# quadcopter.net
KiCad netlist of a schematic drawn in EAGLE
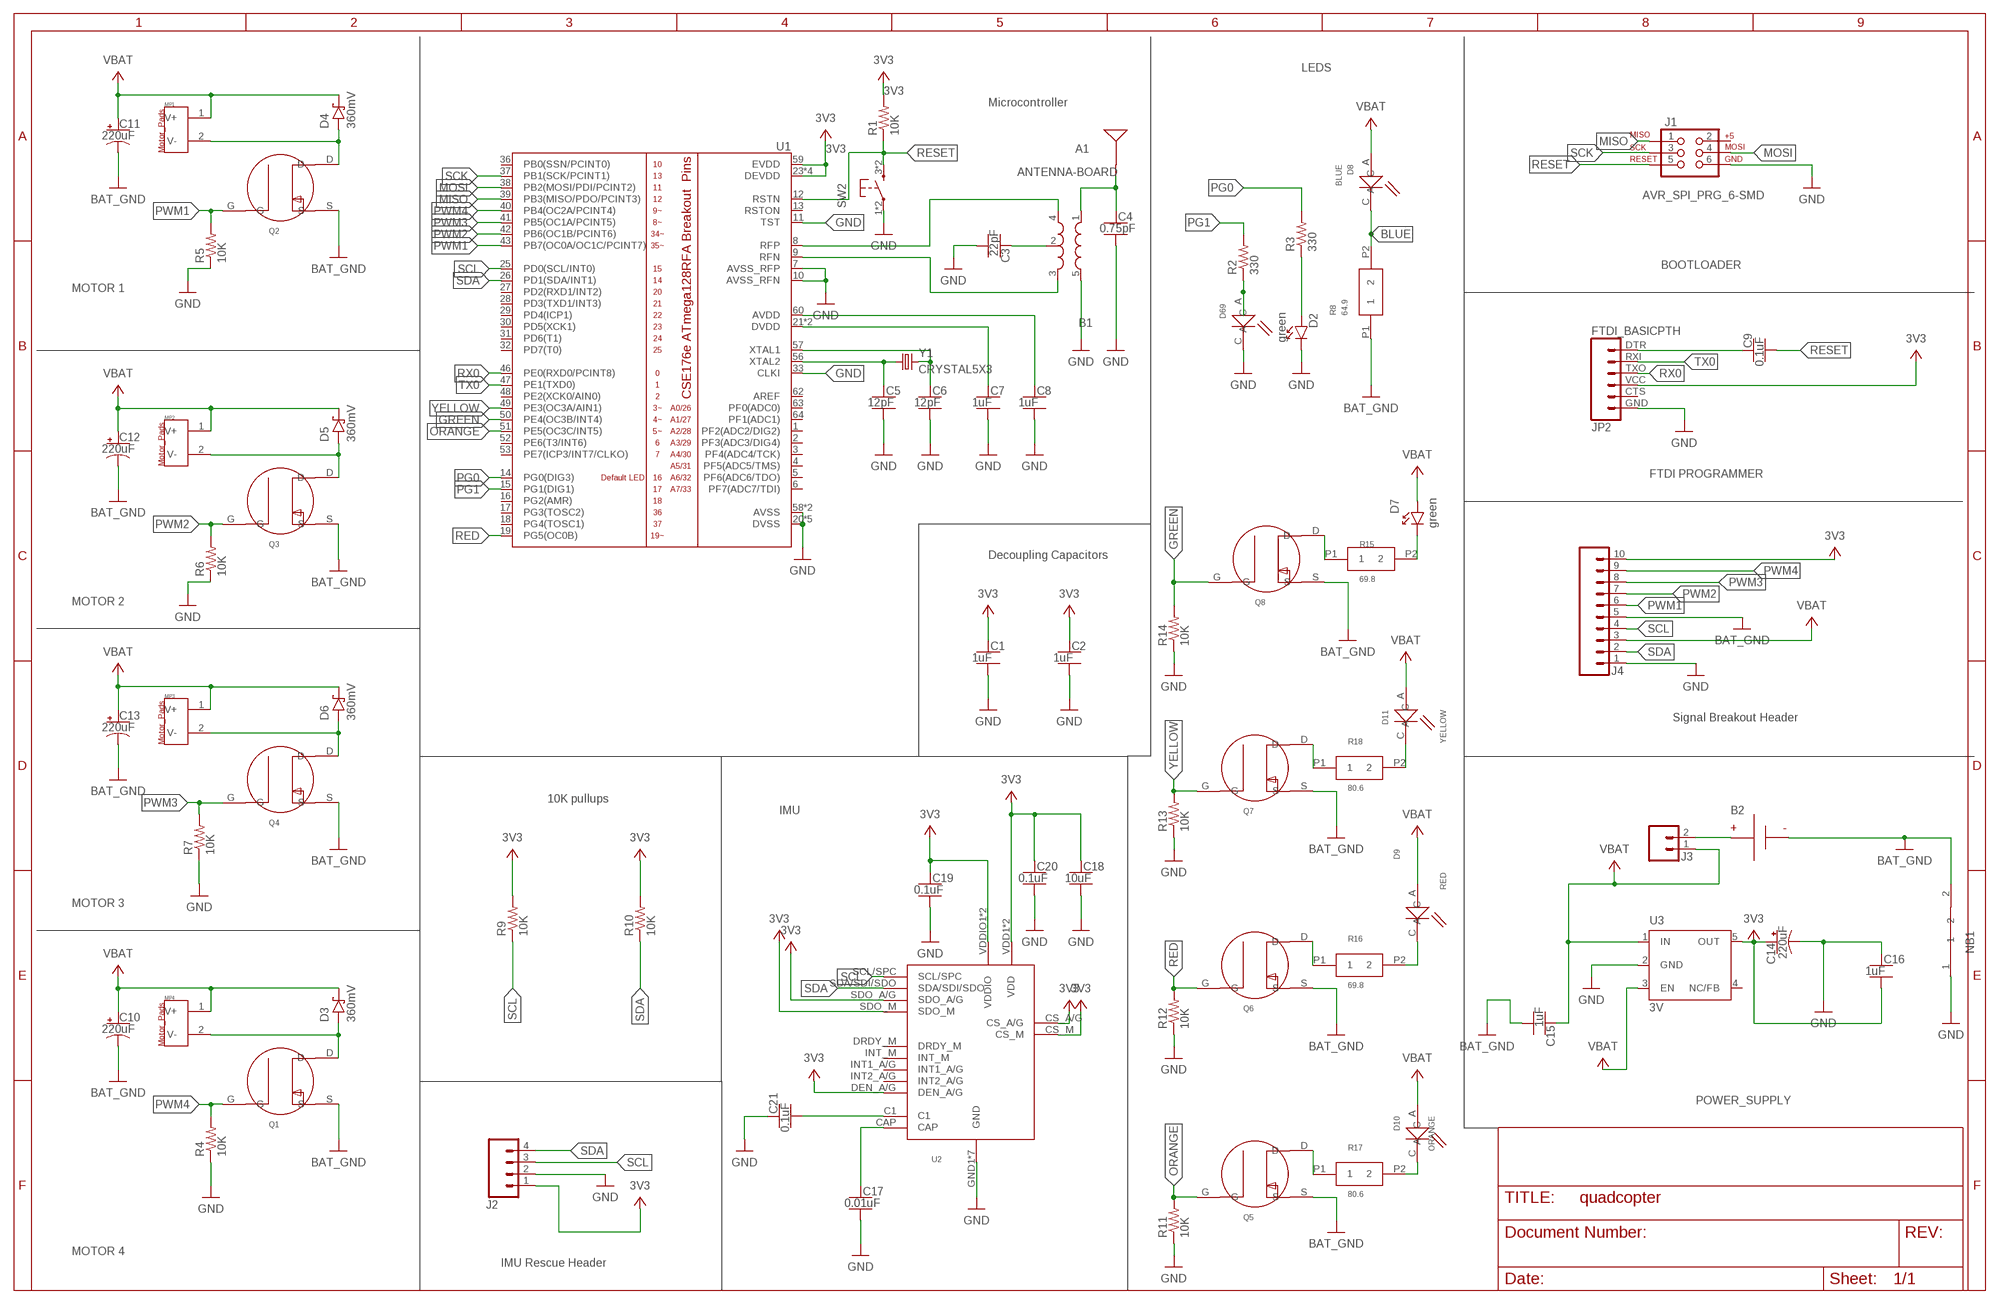
[diagram p0: schematic, sheet 1]

(export (version "E")
  (design (tool "Eeschema 10.0.6"))
  (components
    (comp (ref "A1")
      (value "ANTENNA-BOARD")
      (footprint "eagle-import:ANT_PCB_2.4GHZ_NRF8001_1.6MM_1OZ")
      (fields (field (name "CREATOR") "Swanson"))
      (libsource (lib "eagle-import") (part "ANTENNA-BOARD"))
    )
    (comp (ref "B1")
      (value "BALUN0805")
      (footprint "eagle-import:BALUN")
      (fields
        (field (name "MFR") "Wurth Electronics Inc")
        (field (name "MPN") "748421245")
        (field (name "CREATOR") "Swanson")
        (field (name "REVIEWER") "Swanson")
      )
      (libsource (lib "eagle-import") (part "BALUN0805"))
    )
    (comp (ref "B2")
      (value "BATTERY-SCREW-TERMINAL")
      (footprint "eagle-import:SCREW-TERMINAL-1X2-2.54MM")
      (fields (field (name "CREATOR") "Swanson"))
      (libsource (lib "eagle-import") (part "BATTERY-SCREW-TERMINAL"))
    )
    (comp (ref "C1")
      (value "1uF")
      (footprint "eagle-import:CAPC2012X140_HS")
      (fields
        (field (name "MFR") "Taiyo Yuden")
        (field (name "MPN") "TMK212B7105KG-T")
        (field (name "CREATOR") "Swanson")
        (field (name "REVIEWER") "Swanson")
      )
      (libsource (lib "eagle-import") (part "CAPACITOR-NP_SMD-2012-0805_CERAMIC-1UF"))
    )
    (comp (ref "C2")
      (value "1uF")
      (footprint "eagle-import:CAPC2012X140_HS")
      (fields
        (field (name "MFR") "Taiyo Yuden")
        (field (name "MPN") "TMK212B7105KG-T")
        (field (name "CREATOR") "Swanson")
        (field (name "REVIEWER") "Swanson")
      )
      (libsource (lib "eagle-import") (part "CAPACITOR-NP_SMD-2012-0805_CERAMIC-1UF"))
    )
    (comp (ref "C3")
      (value "22pF")
      (footprint "eagle-import:CAPC2012X140_HS")
      (fields
        (field (name "MFR") "Murata Electronics North America")
        (field (name "MPN") "GRM21A5C2E220JW01D")
        (field (name "CREATOR") "Swanson")
        (field (name "REVIEWER") "Swanson")
      )
      (libsource (lib "eagle-import") (part "CAPACITOR-NP_SMD-2012-0805_CERAMIC-22PF"))
    )
    (comp (ref "C4")
      (value "0.75pF")
      (footprint "eagle-import:CAPC2012X140_HS")
      (fields
        (field (name "MFR") "Murata Electronics North America")
        (field (name "MPN") "GQM2195C2AR75CB01D")
        (field (name "CREATOR") "Swanson")
        (field (name "REVIEWER") "Swanson")
      )
      (libsource (lib "eagle-import") (part "CAPACITOR-NP_SMD-2012-0805_CERAMIC-0.75PF"))
    )
    (comp (ref "C5")
      (value "12pF")
      (footprint "eagle-import:CAPC2012X140_HS")
      (fields
        (field (name "MFR") "Murata Electronics North America")
        (field (name "MPN") "GRM21A5C2E120JW01D")
        (field (name "CREATOR") "Swanson")
        (field (name "REVIEWER") "Swanson")
      )
      (libsource (lib "eagle-import") (part "CAPACITOR-NP_SMD-2012-0805_CERAMIC-12PF"))
    )
    (comp (ref "C6")
      (value "12pF")
      (footprint "eagle-import:CAPC2012X140_HS")
      (fields
        (field (name "MFR") "Murata Electronics North America")
        (field (name "MPN") "GRM21A5C2E120JW01D")
        (field (name "CREATOR") "Swanson")
        (field (name "REVIEWER") "Swanson")
      )
      (libsource (lib "eagle-import") (part "CAPACITOR-NP_SMD-2012-0805_CERAMIC-12PF"))
    )
    (comp (ref "C7")
      (value "1uF")
      (footprint "eagle-import:CAPC2012X140_HS")
      (fields
        (field (name "MFR") "Taiyo Yuden")
        (field (name "MPN") "TMK212B7105KG-T")
        (field (name "CREATOR") "Swanson")
        (field (name "REVIEWER") "Swanson")
      )
      (libsource (lib "eagle-import") (part "CAPACITOR-NP_SMD-2012-0805_CERAMIC-1UF"))
    )
    (comp (ref "C8")
      (value "1uF")
      (footprint "eagle-import:CAPC2012X140_HS")
      (fields
        (field (name "MFR") "Taiyo Yuden")
        (field (name "MPN") "TMK212B7105KG-T")
        (field (name "CREATOR") "Swanson")
        (field (name "REVIEWER") "Swanson")
      )
      (libsource (lib "eagle-import") (part "CAPACITOR-NP_SMD-2012-0805_CERAMIC-1UF"))
    )
    (comp (ref "C9")
      (value "0.1uF")
      (footprint "eagle-import:CAPC2012X140_HS")
      (fields
        (field (name "MFR") "TDK")
        (field (name "MPN") "C2012X7R2A104K125AA")
        (field (name "CREATOR") "Swanson")
        (field (name "REVIEWER") "Swanson")
      )
      (libsource (lib "eagle-import") (part "CAPACITOR-NP_SMD-2012-0805_CERAMIC-0.1UF"))
    )
    (comp (ref "C10")
      (value "220uF")
      (footprint "eagle-import:CAPMP7343X310_HS")
      (fields
        (field (name "MFR") "AVX Corporation")
        (field (name "MPN") "TAJD227K006RNJ")
        (field (name "CREATOR") "Swanson")
        (field (name "REVIEWER") "Swanson")
      )
      (libsource (lib "eagle-import") (part "CAPACITOR-POL_SMD-7043-D_TANTALUM-220UF"))
    )
    (comp (ref "C11")
      (value "220uF")
      (footprint "eagle-import:CAPMP7343X310_HS")
      (fields
        (field (name "MFR") "AVX Corporation")
        (field (name "MPN") "TAJD227K006RNJ")
        (field (name "CREATOR") "Swanson")
        (field (name "REVIEWER") "Swanson")
      )
      (libsource (lib "eagle-import") (part "CAPACITOR-POL_SMD-7043-D_TANTALUM-220UF"))
    )
    (comp (ref "C12")
      (value "220uF")
      (footprint "eagle-import:CAPMP7343X310_HS")
      (fields
        (field (name "MFR") "AVX Corporation")
        (field (name "MPN") "TAJD227K006RNJ")
        (field (name "CREATOR") "Swanson")
        (field (name "REVIEWER") "Swanson")
      )
      (libsource (lib "eagle-import") (part "CAPACITOR-POL_SMD-7043-D_TANTALUM-220UF"))
    )
    (comp (ref "C13")
      (value "220uF")
      (footprint "eagle-import:CAPMP7343X310_HS")
      (fields
        (field (name "MFR") "AVX Corporation")
        (field (name "MPN") "TAJD227K006RNJ")
        (field (name "CREATOR") "Swanson")
        (field (name "REVIEWER") "Swanson")
      )
      (libsource (lib "eagle-import") (part "CAPACITOR-POL_SMD-7043-D_TANTALUM-220UF"))
    )
    (comp (ref "C14")
      (value "220uF")
      (footprint "eagle-import:CAPMP7343X310_HS")
      (fields
        (field (name "MFR") "AVX Corporation")
        (field (name "MPN") "TAJD227K006RNJ")
        (field (name "CREATOR") "Swanson")
        (field (name "REVIEWER") "Swanson")
      )
      (libsource (lib "eagle-import") (part "CAPACITOR-POL_SMD-7043-D_TANTALUM-220UF"))
    )
    (comp (ref "C15")
      (value "1uF")
      (footprint "eagle-import:CAPC2012X140_HS")
      (fields
        (field (name "MFR") "Taiyo Yuden")
        (field (name "MPN") "TMK212B7105KG-T")
        (field (name "CREATOR") "Swanson")
        (field (name "REVIEWER") "Swanson")
      )
      (libsource (lib "eagle-import") (part "CAPACITOR-NP_SMD-2012-0805_CERAMIC-1UF"))
    )
    (comp (ref "C16")
      (value "1uF")
      (footprint "eagle-import:CAPC2012X140_HS")
      (fields
        (field (name "MFR") "Taiyo Yuden")
        (field (name "MPN") "TMK212B7105KG-T")
        (field (name "CREATOR") "Swanson")
        (field (name "REVIEWER") "Swanson")
      )
      (libsource (lib "eagle-import") (part "CAPACITOR-NP_SMD-2012-0805_CERAMIC-1UF"))
    )
    (comp (ref "C17")
      (value "0.01uF")
      (footprint "eagle-import:CAPC2012X140_HS")
      (fields
        (field (name "MFR") "Knowles Syfer")
        (field (name "MPN") "0805J0500104KJT")
        (field (name "CREATOR") "Swanson")
        (field (name "REVIEWER") "Swanson")
      )
      (libsource (lib "eagle-import") (part "CAPACITOR-NP_SMD-2012-0805_CERAMIC-0.01UF"))
    )
    (comp (ref "C18")
      (value "10uF")
      (footprint "eagle-import:CAPC2012X140_HS")
      (fields (field (name "CREATOR") "Swanson") (field (name "REVIEWER") "Swanson"))
      (libsource (lib "eagle-import") (part "CAPACITOR-NP_SMD-2012-0805_CERAMIC-10UF"))
    )
    (comp (ref "C19")
      (value "0.1uF")
      (footprint "eagle-import:CAPC2012X140_HS")
      (fields
        (field (name "MFR") "TDK")
        (field (name "MPN") "C2012X7R2A104K125AA")
        (field (name "CREATOR") "Swanson")
        (field (name "REVIEWER") "Swanson")
      )
      (libsource (lib "eagle-import") (part "CAPACITOR-NP_SMD-2012-0805_CERAMIC-0.1UF"))
    )
    (comp (ref "C20")
      (value "0.1uF")
      (footprint "eagle-import:CAPC2012X140_HS")
      (fields
        (field (name "MFR") "TDK")
        (field (name "MPN") "C2012X7R2A104K125AA")
        (field (name "CREATOR") "Swanson")
        (field (name "REVIEWER") "Swanson")
      )
      (libsource (lib "eagle-import") (part "CAPACITOR-NP_SMD-2012-0805_CERAMIC-0.1UF"))
    )
    (comp (ref "C21")
      (value "0.1uF")
      (footprint "eagle-import:CAPC2012X140_HS")
      (fields
        (field (name "MFR") "TDK")
        (field (name "MPN") "C2012X7R2A104K125AA")
        (field (name "CREATOR") "Swanson")
        (field (name "REVIEWER") "Swanson")
      )
      (libsource (lib "eagle-import") (part "CAPACITOR-NP_SMD-2012-0805_CERAMIC-0.1UF"))
    )
    (comp (ref "D2")
      (value "green")
      (footprint "eagle-import:LEDSC125X200X120-2_HS")
      (fields
        (field (name "MFR") "Lite-On Inc")
        (field (name "MPN") "LTST-C170GKT")
        (field (name "CREATOR") "Swanson")
        (field (name "REVIEWER") "Swanson")
      )
      (libsource (lib "eagle-import") (part "DIODE-LED_SMD-2012-0805-GREEN"))
    )
    (comp (ref "D3")
      (value "360mV")
      (footprint "eagle-import:SOD3716X135_HS")
      (fields
        (field (name "MFR") "Toshiba Semiconductor and Storage")
        (field (name "MPN") "CRS08(TE85L,Q,M)")
        (field (name "CREATOR") "Swanson")
        (field (name "REVIEWER") "Swanson")
      )
      (libsource (lib "eagle-import") (part "DIODE-SCHOTTKY_SMD-SOD123-360MV"))
    )
    (comp (ref "D4")
      (value "360mV")
      (footprint "eagle-import:SOD3716X135_HS")
      (fields
        (field (name "MFR") "Toshiba Semiconductor and Storage")
        (field (name "MPN") "CRS08(TE85L,Q,M)")
        (field (name "CREATOR") "Swanson")
        (field (name "REVIEWER") "Swanson")
      )
      (libsource (lib "eagle-import") (part "DIODE-SCHOTTKY_SMD-SOD123-360MV"))
    )
    (comp (ref "D5")
      (value "360mV")
      (footprint "eagle-import:SOD3716X135_HS")
      (fields
        (field (name "MFR") "Toshiba Semiconductor and Storage")
        (field (name "MPN") "CRS08(TE85L,Q,M)")
        (field (name "CREATOR") "Swanson")
        (field (name "REVIEWER") "Swanson")
      )
      (libsource (lib "eagle-import") (part "DIODE-SCHOTTKY_SMD-SOD123-360MV"))
    )
    (comp (ref "D6")
      (value "360mV")
      (footprint "eagle-import:SOD3716X135_HS")
      (fields
        (field (name "MFR") "Toshiba Semiconductor and Storage")
        (field (name "MPN") "CRS08(TE85L,Q,M)")
        (field (name "CREATOR") "Swanson")
        (field (name "REVIEWER") "Swanson")
      )
      (libsource (lib "eagle-import") (part "DIODE-SCHOTTKY_SMD-SOD123-360MV"))
    )
    (comp (ref "D7")
      (value "green")
      (footprint "eagle-import:LEDSC125X200X120-2_HS")
      (fields
        (field (name "MFR") "Lite-On Inc")
        (field (name "MPN") "LTST-C170GKT")
        (field (name "CREATOR") "Swanson")
        (field (name "REVIEWER") "Swanson")
      )
      (libsource (lib "eagle-import") (part "DIODE-LED_SMD-2012-0805-GREEN"))
    )
    (comp (ref "D8")
      (value "BLUE")
      (footprint "eagle-import:0805_LED")
      (fields (field (name "CREATOR") "robntom"))
      (libsource (lib "eagle-import") (part "LED-BLUE"))
    )
    (comp (ref "D9")
      (value "RED")
      (footprint "eagle-import:0805_LED")
      (fields (field (name "CREATOR") "robntom"))
      (libsource (lib "eagle-import") (part "LEDRED"))
    )
    (comp (ref "D10")
      (value "ORANGE")
      (footprint "eagle-import:0805_LED")
      (fields (field (name "CREATOR") "ROBTOM"))
      (libsource (lib "eagle-import") (part "LED-ORANGE"))
    )
    (comp (ref "D11")
      (value "YELLOW")
      (footprint "eagle-import:0805_LED")
      (fields (field (name "CREATOR") "ROBTOM"))
      (libsource (lib "eagle-import") (part "LED-YELLOW"))
    )
    (comp (ref "D69")
      (value "LEDRED")
      (footprint "eagle-import:0805_LED")
      (fields (field (name "CREATOR") "robntom"))
      (libsource (lib "eagle-import") (part "LEDRED"))
    )
    (comp (ref "J1")
      (value "AVR_SPI_PRG_6-SMD")
      (footprint "eagle-import:2X3-SMD")
      (fields (field (name "CREATOR") "Swanson"))
      (libsource (lib "eagle-import") (part "AVR_SPI_PRG_6-SMD"))
    )
    (comp (ref "J2")
      (value "HEADER-4POS-0.1IN-FEMALE")
      (footprint "eagle-import:HDRVR4W80P254_1X4_1066X254X850B")
      (fields (field (name "CREATOR") "Swanson"))
      (libsource (lib "eagle-import") (part "HEADER-4POS-0.1IN-FEMALE"))
    )
    (comp (ref "J3")
      (value "HEADER-0.1IN-2POS-MALE")
      (footprint "eagle-import:HDRV2W63P254_2X1_508X254H838_HS")
      (fields (field (name "CREATOR") "Swanson"))
      (libsource (lib "eagle-import") (part "HEADER-0.1IN-2POS-MALE"))
    )
    (comp (ref "J4")
      (value "HEADER-10POSTH-254X10")
      (footprint "eagle-import:HDRV10W63P254_10X1_2540X254H838_HS")
      (fields
        (field (name "MFR") "Amphenol FCI")
        (field (name "MPN") "68000-110HLF")
        (field (name "CREATOR") "Swanson")
        (field (name "REVIEWER") "Swanson")
      )
      (libsource (lib "eagle-import") (part "HEADER-10POSTH-254X10"))
    )
    (comp (ref "JP2")
      (value "FTDI_BASICPTH")
      (footprint "eagle-import:FTDI_BASIC")
      (fields
        (field (name "MFR") "Amphenol FCI")
        (field (name "MPN") "68016-406HLF")
        (field (name "CREATOR") "Swanson")
        (field (name "REVIEWER") "Swanson")
      )
      (libsource (lib "eagle-import") (part "FTDI_BASICPTH"))
    )
    (comp (ref "MP1")
      (value "MOTOR_PADS-MOLEX-0530470210")
      (footprint "eagle-import:MOLEX-0530470210")
      (fields (field (name "CREATOR") "Swanson"))
      (libsource (lib "eagle-import") (part "MOTOR_PADS-MOLEX-0530470210"))
    )
    (comp (ref "MP2")
      (value "MOTOR_PADS-MOLEX-0530470210")
      (footprint "eagle-import:MOLEX-0530470210")
      (fields (field (name "CREATOR") "Swanson"))
      (libsource (lib "eagle-import") (part "MOTOR_PADS-MOLEX-0530470210"))
    )
    (comp (ref "MP3")
      (value "MOTOR_PADS-MOLEX-0530470210")
      (footprint "eagle-import:MOLEX-0530470210")
      (fields (field (name "CREATOR") "Swanson"))
      (libsource (lib "eagle-import") (part "MOTOR_PADS-MOLEX-0530470210"))
    )
    (comp (ref "MP4")
      (value "MOTOR_PADS-MOLEX-0530470210")
      (footprint "eagle-import:MOLEX-0530470210")
      (fields (field (name "CREATOR") "Swanson"))
      (libsource (lib "eagle-import") (part "MOTOR_PADS-MOLEX-0530470210"))
    )
    (comp (ref "NB1")
      (value "NETBRIDGE")
      (footprint "eagle-import:NET_BRIDGE")
      (fields (field (name "CREATOR") "tom+rob"))
      (libsource (lib "eagle-import") (part "NETBRIDGE"))
    )
    (comp (ref "Q1")
      (value "NMOSFET-NMOSFET")
      (footprint "eagle-import:N-CH_MOSFET")
      (fields (field (name "CREATOR") "rketch"))
      (libsource (lib "eagle-import") (part "NMOSFET-NMOSFET"))
    )
    (comp (ref "Q2")
      (value "NMOSFET-NMOSFET")
      (footprint "eagle-import:N-CH_MOSFET")
      (fields (field (name "CREATOR") "rketch"))
      (libsource (lib "eagle-import") (part "NMOSFET-NMOSFET"))
    )
    (comp (ref "Q3")
      (value "NMOSFET-NMOSFET")
      (footprint "eagle-import:N-CH_MOSFET")
      (fields (field (name "CREATOR") "rketch"))
      (libsource (lib "eagle-import") (part "NMOSFET-NMOSFET"))
    )
    (comp (ref "Q4")
      (value "NMOSFET-NMOSFET")
      (footprint "eagle-import:N-CH_MOSFET")
      (fields (field (name "CREATOR") "rketch"))
      (libsource (lib "eagle-import") (part "NMOSFET-NMOSFET"))
    )
    (comp (ref "Q5")
      (value "NMOSFET-NMOSFET")
      (footprint "eagle-import:N-CH_MOSFET")
      (fields (field (name "CREATOR") "rketch"))
      (libsource (lib "eagle-import") (part "NMOSFET-NMOSFET"))
    )
    (comp (ref "Q6")
      (value "NMOSFET-NMOSFET")
      (footprint "eagle-import:N-CH_MOSFET")
      (fields (field (name "CREATOR") "rketch"))
      (libsource (lib "eagle-import") (part "NMOSFET-NMOSFET"))
    )
    (comp (ref "Q7")
      (value "NMOSFET-NMOSFET")
      (footprint "eagle-import:N-CH_MOSFET")
      (fields (field (name "CREATOR") "rketch"))
      (libsource (lib "eagle-import") (part "NMOSFET-NMOSFET"))
    )
    (comp (ref "Q8")
      (value "NMOSFET-NMOSFET")
      (footprint "eagle-import:N-CH_MOSFET")
      (fields (field (name "CREATOR") "rketch"))
      (libsource (lib "eagle-import") (part "NMOSFET-NMOSFET"))
    )
    (comp (ref "R1")
      (value "10K")
      (footprint "eagle-import:RESC2012X60_HS")
      (fields
        (field (name "MFR") "Yageo")
        (field (name "MPN") "RC0805JR-0710KL")
        (field (name "CREATOR") "Swanson")
        (field (name "REVIEWER") "Swanson")
      )
      (libsource (lib "eagle-import") (part "RESISTOR_SMD-2012-0805-10K"))
    )
    (comp (ref "R2")
      (value "330")
      (footprint "eagle-import:RESC2012X60_HS")
      (fields
        (field (name "MFR") "Yageo")
        (field (name "MPN") "RC0805JR-07330RL")
        (field (name "CREATOR") "Swanson")
        (field (name "REVIEWER") "Swanson")
      )
      (libsource (lib "eagle-import") (part "RESISTOR_SMD-2012-0805-330"))
    )
    (comp (ref "R3")
      (value "330")
      (footprint "eagle-import:RESC2012X60_HS")
      (fields
        (field (name "MFR") "Yageo")
        (field (name "MPN") "RC0805JR-07330RL")
        (field (name "CREATOR") "Swanson")
        (field (name "REVIEWER") "Swanson")
      )
      (libsource (lib "eagle-import") (part "RESISTOR_SMD-2012-0805-330"))
    )
    (comp (ref "R4")
      (value "10K")
      (footprint "eagle-import:RESC2012X60_HS")
      (fields
        (field (name "MFR") "Yageo")
        (field (name "MPN") "RC0805JR-0710KL")
        (field (name "CREATOR") "Swanson")
        (field (name "REVIEWER") "Swanson")
      )
      (libsource (lib "eagle-import") (part "RESISTOR_SMD-2012-0805-10K"))
    )
    (comp (ref "R5")
      (value "10K")
      (footprint "eagle-import:RESC2012X60_HS")
      (fields
        (field (name "MFR") "Yageo")
        (field (name "MPN") "RC0805JR-0710KL")
        (field (name "CREATOR") "Swanson")
        (field (name "REVIEWER") "Swanson")
      )
      (libsource (lib "eagle-import") (part "RESISTOR_SMD-2012-0805-10K"))
    )
    (comp (ref "R6")
      (value "10K")
      (footprint "eagle-import:RESC2012X60_HS")
      (fields
        (field (name "MFR") "Yageo")
        (field (name "MPN") "RC0805JR-0710KL")
        (field (name "CREATOR") "Swanson")
        (field (name "REVIEWER") "Swanson")
      )
      (libsource (lib "eagle-import") (part "RESISTOR_SMD-2012-0805-10K"))
    )
    (comp (ref "R7")
      (value "10K")
      (footprint "eagle-import:RESC2012X60_HS")
      (fields
        (field (name "MFR") "Yageo")
        (field (name "MPN") "RC0805JR-0710KL")
        (field (name "CREATOR") "Swanson")
        (field (name "REVIEWER") "Swanson")
      )
      (libsource (lib "eagle-import") (part "RESISTOR_SMD-2012-0805-10K"))
    )
    (comp (ref "R8")
      (value "64.9")
      (footprint "eagle-import:0805_RESISTOR")
      (fields (field (name "CREATOR") "ROBTOM"))
      (libsource (lib "eagle-import") (part "RESISTOR-64.9OHM"))
    )
    (comp (ref "R9")
      (value "10K")
      (footprint "eagle-import:RESC2012X60_HS")
      (fields
        (field (name "MFR") "Yageo")
        (field (name "MPN") "RC0805JR-0710KL")
        (field (name "CREATOR") "Swanson")
        (field (name "REVIEWER") "Swanson")
      )
      (libsource (lib "eagle-import") (part "RESISTOR_SMD-2012-0805-10K"))
    )
    (comp (ref "R10")
      (value "10K")
      (footprint "eagle-import:RESC2012X60_HS")
      (fields
        (field (name "MFR") "Yageo")
        (field (name "MPN") "RC0805JR-0710KL")
        (field (name "CREATOR") "Swanson")
        (field (name "REVIEWER") "Swanson")
      )
      (libsource (lib "eagle-import") (part "RESISTOR_SMD-2012-0805-10K"))
    )
    (comp (ref "R11")
      (value "10K")
      (footprint "eagle-import:RESC2012X60_HS")
      (fields
        (field (name "MFR") "Yageo")
        (field (name "MPN") "RC0805JR-0710KL")
        (field (name "CREATOR") "Swanson")
        (field (name "REVIEWER") "Swanson")
      )
      (libsource (lib "eagle-import") (part "RESISTOR_SMD-2012-0805-10K"))
    )
    (comp (ref "R12")
      (value "10K")
      (footprint "eagle-import:RESC2012X60_HS")
      (fields
        (field (name "MFR") "Yageo")
        (field (name "MPN") "RC0805JR-0710KL")
        (field (name "CREATOR") "Swanson")
        (field (name "REVIEWER") "Swanson")
      )
      (libsource (lib "eagle-import") (part "RESISTOR_SMD-2012-0805-10K"))
    )
    (comp (ref "R13")
      (value "10K")
      (footprint "eagle-import:RESC2012X60_HS")
      (fields
        (field (name "MFR") "Yageo")
        (field (name "MPN") "RC0805JR-0710KL")
        (field (name "CREATOR") "Swanson")
        (field (name "REVIEWER") "Swanson")
      )
      (libsource (lib "eagle-import") (part "RESISTOR_SMD-2012-0805-10K"))
    )
    (comp (ref "R14")
      (value "10K")
      (footprint "eagle-import:RESC2012X60_HS")
      (fields
        (field (name "MFR") "Yageo")
        (field (name "MPN") "RC0805JR-0710KL")
        (field (name "CREATOR") "Swanson")
        (field (name "REVIEWER") "Swanson")
      )
      (libsource (lib "eagle-import") (part "RESISTOR_SMD-2012-0805-10K"))
    )
    (comp (ref "R15")
      (value "69.8")
      (footprint "eagle-import:0805_RESISTOR")
      (fields (field (name "CREATOR") "ROBTOM"))
      (libsource (lib "eagle-import") (part "RESISTOR-69.8OHM"))
    )
    (comp (ref "R16")
      (value "69.8")
      (footprint "eagle-import:0805_RESISTOR")
      (fields (field (name "CREATOR") "ROBTOM"))
      (libsource (lib "eagle-import") (part "RESISTOR-69.8OHM"))
    )
    (comp (ref "R17")
      (value "80.6")
      (footprint "eagle-import:0805_RESISTOR")
      (fields (field (name "CREATOR") "ROBTOM"))
      (libsource (lib "eagle-import") (part "RESISTOR-80.6OHM"))
    )
    (comp (ref "R18")
      (value "80.6")
      (footprint "eagle-import:0805_RESISTOR")
      (fields (field (name "CREATOR") "ROBTOM"))
      (libsource (lib "eagle-import") (part "RESISTOR-80.6OHM"))
    )
    (comp (ref "SW2")
      (value "PUSHBUTTON_-4.5X4.5")
      (footprint "eagle-import:4.5MM_TACTILE_SWITCH_TL3305AF160QG")
      (fields (field (name "CREATOR") "Swanson"))
      (libsource (lib "eagle-import") (part "PUSHBUTTON_-4.5X4.5"))
    )
    (comp (ref "U1")
      (value "ATMEGA128RFA1")
      (footprint "eagle-import:QFN-64")
      (fields
        (field (name "MFR") "Atmel")
        (field (name "MPN") "ATMEGA128RFA1-ZUR00")
        (field (name "CREATOR") "Swanson")
        (field (name "REVIEWER") "Swanson")
      )
      (libsource (lib "eagle-import") (part "ATMEGA128RFA1"))
    )
    (comp (ref "U2")
      (value "LSM9DS1TR9AXISIMU-ACCEL/GYRO/MAGI2C/SPI24LGA")
      (footprint "eagle-import:LSM9DS1TR9-AXISIMU")
      (fields (field (name "CREATOR") "rketch"))
      (libsource (lib "eagle-import") (part "LSM9DS1TR9AXISIMU-ACCEL/GYRO/MAGI2C/SPI24LGA"))
    )
    (comp (ref "U3")
      (value "3V")
      (footprint "eagle-import:SOT23-DBV")
      (fields
        (field (name "MFR") "Texas Instruments")
        (field (name "MPN") "LP3985IM5X-3.0/NOPB")
        (field (name "CREATOR") "Swanson")
        (field (name "REVIEWER") "Swanson")
      )
      (libsource (lib "eagle-import") (part "TPS73633-DBVT3V"))
    )
    (comp (ref "Y1")
      (value "CRYSTAL5X3")
      (footprint "eagle-import:CRYSTAL-SMD-5X3")
      (fields
        (field (name "MFR") "Abracon LLC")
        (field (name "MPN") "ABM3B-16.000MHZ-B2-T")
        (field (name "CREATOR") "Swanson")
        (field (name "REVIEWER") "Swanson")
      )
      (libsource (lib "eagle-import") (part "CRYSTAL5X3"))
    )
  )
  (nets
    (net (code "1") (name "3V3") (class "Default")
      (node (ref "C1") (pin "1") (pinfunction "1_1") (pintype "passive"))
      (node (ref "C14") (pin "1") (pinfunction "+_1") (pintype "passive"))
      (node (ref "C16") (pin "2") (pinfunction "2_2") (pintype "passive"))
      (node (ref "C18") (pin "1") (pinfunction "1_1") (pintype "passive"))
      (node (ref "C19") (pin "1") (pinfunction "1_1") (pintype "passive"))
      (node (ref "C2") (pin "1") (pinfunction "1_1") (pintype "passive"))
      (node (ref "C20") (pin "1") (pinfunction "1_1") (pintype "passive"))
      (node (ref "J2") (pin "1") (pinfunction "1_1") (pintype "bidirectional"))
      (node (ref "J4") (pin "10") (pinfunction "10_10") (pintype "passive"))
      (node (ref "JP2") (pin "VCC") (pinfunction "4_VCC") (pintype "passive"))
      (node (ref "R1") (pin "2") (pinfunction "2_2") (pintype "passive"))
      (node (ref "R10") (pin "2") (pinfunction "2_2") (pintype "passive"))
      (node (ref "R9") (pin "2") (pinfunction "2_2") (pintype "passive"))
      (node (ref "U1") (pin "23") (pinfunction "DEVDD_23") (pintype "bidirectional"))
      (node (ref "U1") (pin "34") (pinfunction "DEVDD_34") (pintype "bidirectional"))
      (node (ref "U1") (pin "44") (pinfunction "DEVDD_44") (pintype "bidirectional"))
      (node (ref "U1") (pin "54") (pinfunction "DEVDD_54") (pintype "bidirectional"))
      (node (ref "U1") (pin "59") (pinfunction "EVDD_59") (pintype "bidirectional"))
      (node (ref "U2") (pin "CS_A/G") (pinfunction "CS_A/G_CS_A/G") (pintype "bidirectional"))
      (node (ref "U2") (pin "CS_M") (pinfunction "CS_M_CS_M") (pintype "bidirectional"))
      (node (ref "U2") (pin "DEN_A/G") (pinfunction "DEN_A/G_DEN_A/G") (pintype "bidirectional"))
      (node (ref "U2") (pin "SDO_A/G") (pinfunction "SDO_A/G_SDO_A/G") (pintype "bidirectional"))
      (node (ref "U2") (pin "SDO_M") (pinfunction "SDO_M_SDO_M") (pintype "bidirectional"))
      (node (ref "U2") (pin "VDD1") (pinfunction "VDD_VDD1") (pintype "bidirectional"))
      (node (ref "U2") (pin "VDD2") (pinfunction "VDD_VDD2") (pintype "bidirectional"))
      (node (ref "U2") (pin "VDDIO1") (pinfunction "VDDIO_VDDIO1") (pintype "bidirectional"))
      (node (ref "U2") (pin "VDDIO2") (pinfunction "VDDIO_VDDIO2") (pintype "bidirectional"))
      (node (ref "U3") (pin "5") (pinfunction "OUT_5") (pintype "passive"))
    )
    (net (code "2") (name "BAT_GND") (class "Default")
      (node (ref "B2") (pin "1") (pinfunction "N_1") (pintype "bidirectional"))
      (node (ref "C10") (pin "2") (pinfunction "-_2") (pintype "passive"))
      (node (ref "C11") (pin "2") (pinfunction "-_2") (pintype "passive"))
      (node (ref "C12") (pin "2") (pinfunction "-_2") (pintype "passive"))
      (node (ref "C13") (pin "2") (pinfunction "-_2") (pintype "passive"))
      (node (ref "C15") (pin "2") (pinfunction "2_2") (pintype "passive"))
      (node (ref "J4") (pin "5") (pinfunction "5_5") (pintype "passive"))
      (node (ref "NB1") (pin "2") (pinfunction "2_2") (pintype "bidirectional"))
      (node (ref "Q1") (pin "S") (pinfunction "S_S") (pintype "bidirectional"))
      (node (ref "Q2") (pin "S") (pinfunction "S_S") (pintype "bidirectional"))
      (node (ref "Q3") (pin "S") (pinfunction "S_S") (pintype "bidirectional"))
      (node (ref "Q4") (pin "S") (pinfunction "S_S") (pintype "bidirectional"))
      (node (ref "Q5") (pin "S") (pinfunction "S_S") (pintype "bidirectional"))
      (node (ref "Q6") (pin "S") (pinfunction "S_S") (pintype "bidirectional"))
      (node (ref "Q7") (pin "S") (pinfunction "S_S") (pintype "bidirectional"))
      (node (ref "Q8") (pin "S") (pinfunction "S_S") (pintype "bidirectional"))
      (node (ref "R8") (pin "P1") (pinfunction "1_P1") (pintype "bidirectional"))
    )
    (net (code "3") (name "BLUE") (class "Default")
      (node (ref "D8") (pin "C") (pinfunction "C_C") (pintype "output"))
      (node (ref "R8") (pin "P2") (pinfunction "2_P2") (pintype "bidirectional"))
    )
    (net (code "4") (name "GND") (class "Default")
      (node (ref "B1") (pin "5") (pinfunction "GND_5") (pintype "bidirectional"))
      (node (ref "C1") (pin "2") (pinfunction "2_2") (pintype "passive"))
      (node (ref "C14") (pin "2") (pinfunction "-_2") (pintype "passive"))
      (node (ref "C16") (pin "1") (pinfunction "1_1") (pintype "passive"))
      (node (ref "C17") (pin "2") (pinfunction "2_2") (pintype "passive"))
      (node (ref "C18") (pin "2") (pinfunction "2_2") (pintype "passive"))
      (node (ref "C19") (pin "2") (pinfunction "2_2") (pintype "passive"))
      (node (ref "C2") (pin "2") (pinfunction "2_2") (pintype "passive"))
      (node (ref "C20") (pin "2") (pinfunction "2_2") (pintype "passive"))
      (node (ref "C21") (pin "1") (pinfunction "1_1") (pintype "passive"))
      (node (ref "C3") (pin "2") (pinfunction "2_2") (pintype "passive"))
      (node (ref "C4") (pin "2") (pinfunction "2_2") (pintype "passive"))
      (node (ref "C5") (pin "2") (pinfunction "2_2") (pintype "passive"))
      (node (ref "C6") (pin "2") (pinfunction "2_2") (pintype "passive"))
      (node (ref "C7") (pin "2") (pinfunction "2_2") (pintype "passive"))
      (node (ref "C8") (pin "2") (pinfunction "2_2") (pintype "passive"))
      (node (ref "D2") (pin "C") (pinfunction "C_C") (pintype "passive"))
      (node (ref "D69") (pin "C") (pinfunction "C_C") (pintype "bidirectional"))
      (node (ref "J1") (pin "6") (pinfunction "6_6") (pintype "passive"))
      (node (ref "J2") (pin "2") (pinfunction "2_2") (pintype "bidirectional"))
      (node (ref "J4") (pin "1") (pinfunction "1_1") (pintype "passive"))
      (node (ref "JP2") (pin "GND") (pinfunction "6_GND") (pintype "passive"))
      (node (ref "NB1") (pin "1") (pinfunction "1_1") (pintype "bidirectional"))
      (node (ref "R11") (pin "1") (pinfunction "1_1") (pintype "passive"))
      (node (ref "R12") (pin "1") (pinfunction "1_1") (pintype "passive"))
      (node (ref "R13") (pin "1") (pinfunction "1_1") (pintype "passive"))
      (node (ref "R14") (pin "1") (pinfunction "1_1") (pintype "passive"))
      (node (ref "R4") (pin "1") (pinfunction "1_1") (pintype "passive"))
      (node (ref "R5") (pin "1") (pinfunction "1_1") (pintype "passive"))
      (node (ref "R6") (pin "1") (pinfunction "1_1") (pintype "passive"))
      (node (ref "R7") (pin "1") (pinfunction "1_1") (pintype "passive"))
      (node (ref "SW2") (pin "1") (pinfunction "1_1") (pintype "passive"))
      (node (ref "SW2") (pin "2") (pinfunction "1_2") (pintype "passive"))
      (node (ref "U1") (pin "10") (pinfunction "AVSS_RFN_10") (pintype "bidirectional"))
      (node (ref "U1") (pin "11") (pinfunction "TST_11") (pintype "bidirectional"))
      (node (ref "U1") (pin "20") (pinfunction "DVSS_20") (pintype "bidirectional"))
      (node (ref "U1") (pin "24") (pinfunction "DVSS_24") (pintype "bidirectional"))
      (node (ref "U1") (pin "33") (pinfunction "CLKI_33") (pintype "bidirectional"))
      (node (ref "U1") (pin "35") (pinfunction "DVSS_35") (pintype "bidirectional"))
      (node (ref "U1") (pin "45") (pinfunction "DVSS_45") (pintype "bidirectional"))
      (node (ref "U1") (pin "55") (pinfunction "DVSS_55") (pintype "bidirectional"))
      (node (ref "U1") (pin "58") (pinfunction "AVSS_58") (pintype "bidirectional"))
      (node (ref "U1") (pin "61") (pinfunction "AVSS_61") (pintype "bidirectional"))
      (node (ref "U1") (pin "7") (pinfunction "AVSS_RFP_7") (pintype "bidirectional"))
      (node (ref "U2") (pin "GND1") (pinfunction "GND_GND1") (pintype "bidirectional"))
      (node (ref "U2") (pin "GND2") (pinfunction "GND_GND2") (pintype "bidirectional"))
      (node (ref "U2") (pin "RES1") (pinfunction "GND_RES1") (pintype "bidirectional"))
      (node (ref "U2") (pin "RES2") (pinfunction "GND_RES2") (pintype "bidirectional"))
      (node (ref "U2") (pin "RES3") (pinfunction "GND_RES3") (pintype "bidirectional"))
      (node (ref "U2") (pin "RES4") (pinfunction "GND_RES4") (pintype "bidirectional"))
      (node (ref "U2") (pin "RES5") (pinfunction "GND_RES5") (pintype "bidirectional"))
      (node (ref "U3") (pin "2") (pinfunction "GND_2") (pintype "input"))
    )
    (net (code "5") (name "GREEN") (class "Default")
      (node (ref "Q8") (pin "G") (pinfunction "G_G") (pintype "bidirectional"))
      (node (ref "R14") (pin "2") (pinfunction "2_2") (pintype "passive"))
      (node (ref "U1") (pin "50") (pinfunction "PE4(OC3B/INT4)_50") (pintype "bidirectional"))
    )
    (net (code "6") (name "MISO") (class "Default")
      (node (ref "J1") (pin "1") (pinfunction "1_1") (pintype "passive"))
      (node (ref "U1") (pin "39") (pinfunction "PB3(MISO/PDO/PCINT3)_39") (pintype "bidirectional"))
    )
    (net (code "7") (name "MOSI") (class "Default")
      (node (ref "J1") (pin "4") (pinfunction "4_4") (pintype "passive"))
      (node (ref "U1") (pin "38") (pinfunction "PB2(MOSI/PDI/PCINT2)_38") (pintype "bidirectional"))
    )
    (net (code "8") (name "Net-(A1-SIGNAL)") (class "Default")
      (node (ref "A1") (pin "FEED") (pinfunction "SIGNAL_FEED") (pintype "bidirectional"))
      (node (ref "B1") (pin "1") (pinfunction "IN_1") (pintype "bidirectional"))
      (node (ref "C4") (pin "1") (pinfunction "1_1") (pintype "passive"))
    )
    (net (code "9") (name "Net-(B1-GND-Pad2)") (class "Default")
      (node (ref "B1") (pin "2") (pinfunction "GND_2") (pintype "bidirectional"))
      (node (ref "C3") (pin "1") (pinfunction "1_1") (pintype "passive"))
    )
    (net (code "10") (name "Net-(B1-OUT1)") (class "Default")
      (node (ref "B1") (pin "4") (pinfunction "OUT1_4") (pintype "bidirectional"))
      (node (ref "U1") (pin "8") (pinfunction "RFP_8") (pintype "bidirectional"))
    )
    (net (code "11") (name "Net-(B1-OUT2)") (class "Default")
      (node (ref "B1") (pin "3") (pinfunction "OUT2_3") (pintype "bidirectional"))
      (node (ref "U1") (pin "9") (pinfunction "RFN_9") (pintype "bidirectional"))
    )
    (net (code "12") (name "Net-(B2-P)") (class "Default")
      (node (ref "B2") (pin "2") (pinfunction "P_2") (pintype "bidirectional"))
      (node (ref "J3") (pin "2") (pinfunction "2_2") (pintype "passive"))
    )
    (net (code "13") (name "Net-(C7-Pad1)") (class "Default")
      (node (ref "C7") (pin "1") (pinfunction "1_1") (pintype "passive"))
      (node (ref "U1") (pin "21") (pinfunction "DVDD_21") (pintype "bidirectional"))
      (node (ref "U1") (pin "22") (pinfunction "DVDD_22") (pintype "bidirectional"))
    )
    (net (code "14") (name "Net-(C17-Pad1)") (class "Default")
      (node (ref "C17") (pin "1") (pinfunction "1_1") (pintype "passive"))
      (node (ref "U2") (pin "CAP") (pinfunction "CAP_CAP") (pintype "bidirectional"))
    )
    (net (code "15") (name "Net-(C21-Pad2)") (class "Default")
      (node (ref "C21") (pin "2") (pinfunction "2_2") (pintype "passive"))
      (node (ref "U2") (pin "C1") (pinfunction "C1_C1") (pintype "bidirectional"))
    )
    (net (code "16") (name "Net-(D2-PadA)") (class "Default")
      (node (ref "D2") (pin "A") (pinfunction "A_A") (pintype "passive"))
      (node (ref "R3") (pin "1") (pinfunction "1_1") (pintype "passive"))
    )
    (net (code "17") (name "Net-(D69-PadA)") (class "Default")
      (node (ref "D69") (pin "A") (pinfunction "A_A") (pintype "bidirectional"))
      (node (ref "R2") (pin "1") (pinfunction "1_1") (pintype "passive"))
    )
    (net (code "18") (name "Net-(JP2-1)") (class "Default")
      (node (ref "C9") (pin "1") (pinfunction "1_1") (pintype "passive"))
      (node (ref "JP2") (pin "DTR") (pinfunction "1_DTR") (pintype "passive"))
    )
    (net (code "19") (name "Net-(MP1-V-)") (class "Default")
      (node (ref "D4") (pin "A") (pinfunction "A_A") (pintype "passive"))
      (node (ref "MP1") (pin "2") (pinfunction "V-_2") (pintype "bidirectional"))
      (node (ref "Q2") (pin "D") (pinfunction "D_D") (pintype "bidirectional"))
    )
    (net (code "20") (name "Net-(MP2-V-)") (class "Default")
      (node (ref "D5") (pin "A") (pinfunction "A_A") (pintype "passive"))
      (node (ref "MP2") (pin "2") (pinfunction "V-_2") (pintype "bidirectional"))
      (node (ref "Q3") (pin "D") (pinfunction "D_D") (pintype "bidirectional"))
    )
    (net (code "21") (name "Net-(MP3-V-)") (class "Default")
      (node (ref "D6") (pin "A") (pinfunction "A_A") (pintype "passive"))
      (node (ref "MP3") (pin "2") (pinfunction "V-_2") (pintype "bidirectional"))
      (node (ref "Q4") (pin "D") (pinfunction "D_D") (pintype "bidirectional"))
    )
    (net (code "22") (name "Net-(MP4-V-)") (class "Default")
      (node (ref "D3") (pin "A") (pinfunction "A_A") (pintype "passive"))
      (node (ref "MP4") (pin "2") (pinfunction "V-_2") (pintype "bidirectional"))
      (node (ref "Q1") (pin "D") (pinfunction "D_D") (pintype "bidirectional"))
    )
    (net (code "23") (name "Net-(R15-1)") (class "Default")
      (node (ref "Q8") (pin "D") (pinfunction "D_D") (pintype "bidirectional"))
      (node (ref "R15") (pin "P1") (pinfunction "1_P1") (pintype "bidirectional"))
    )
    (net (code "24") (name "Net-(R15-2)") (class "Default")
      (node (ref "D7") (pin "C") (pinfunction "C_C") (pintype "passive"))
      (node (ref "R15") (pin "P2") (pinfunction "2_P2") (pintype "bidirectional"))
    )
    (net (code "25") (name "Net-(R16-1)") (class "Default")
      (node (ref "Q6") (pin "D") (pinfunction "D_D") (pintype "bidirectional"))
      (node (ref "R16") (pin "P1") (pinfunction "1_P1") (pintype "bidirectional"))
    )
    (net (code "26") (name "Net-(R16-2)") (class "Default")
      (node (ref "D9") (pin "C") (pinfunction "C_C") (pintype "bidirectional"))
      (node (ref "R16") (pin "P2") (pinfunction "2_P2") (pintype "bidirectional"))
    )
    (net (code "27") (name "Net-(R17-1)") (class "Default")
      (node (ref "Q5") (pin "D") (pinfunction "D_D") (pintype "bidirectional"))
      (node (ref "R17") (pin "P1") (pinfunction "1_P1") (pintype "bidirectional"))
    )
    (net (code "28") (name "Net-(R17-2)") (class "Default")
      (node (ref "D10") (pin "C") (pinfunction "C_C") (pintype "output"))
      (node (ref "R17") (pin "P2") (pinfunction "2_P2") (pintype "bidirectional"))
    )
    (net (code "29") (name "Net-(R18-1)") (class "Default")
      (node (ref "Q7") (pin "D") (pinfunction "D_D") (pintype "bidirectional"))
      (node (ref "R18") (pin "P1") (pinfunction "1_P1") (pintype "bidirectional"))
    )
    (net (code "30") (name "Net-(R18-2)") (class "Default")
      (node (ref "D11") (pin "C") (pinfunction "C_C") (pintype "output"))
      (node (ref "R18") (pin "P2") (pinfunction "2_P2") (pintype "bidirectional"))
    )
    (net (code "31") (name "Net-(U1-AVDD)") (class "Default")
      (node (ref "C8") (pin "1") (pinfunction "1_1") (pintype "passive"))
      (node (ref "U1") (pin "60") (pinfunction "AVDD_60") (pintype "bidirectional"))
    )
    (net (code "32") (name "Net-(U1-XTAL1)") (class "Default")
      (node (ref "C6") (pin "1") (pinfunction "1_1") (pintype "passive"))
      (node (ref "U1") (pin "57") (pinfunction "XTAL1_57") (pintype "bidirectional"))
      (node (ref "Y1") (pin "3") (pinfunction "2_3") (pintype "passive"))
    )
    (net (code "33") (name "Net-(U1-XTAL2)") (class "Default")
      (node (ref "C5") (pin "1") (pinfunction "1_1") (pintype "passive"))
      (node (ref "U1") (pin "56") (pinfunction "XTAL2_56") (pintype "bidirectional"))
      (node (ref "Y1") (pin "1") (pinfunction "1_1") (pintype "passive"))
    )
    (net (code "34") (name "ORANGE") (class "Default")
      (node (ref "Q5") (pin "G") (pinfunction "G_G") (pintype "bidirectional"))
      (node (ref "R11") (pin "2") (pinfunction "2_2") (pintype "passive"))
      (node (ref "U1") (pin "51") (pinfunction "PE5(OC3C/INT5)_51") (pintype "bidirectional"))
    )
    (net (code "35") (name "PG0") (class "Default")
      (node (ref "R3") (pin "2") (pinfunction "2_2") (pintype "passive"))
      (node (ref "U1") (pin "14") (pinfunction "PG0(DIG3)_14") (pintype "bidirectional"))
    )
    (net (code "36") (name "PG1") (class "Default")
      (node (ref "R2") (pin "2") (pinfunction "2_2") (pintype "passive"))
      (node (ref "U1") (pin "15") (pinfunction "PG1(DIG1)_15") (pintype "bidirectional"))
    )
    (net (code "37") (name "PWM1") (class "Default")
      (node (ref "J4") (pin "6") (pinfunction "6_6") (pintype "passive"))
      (node (ref "Q2") (pin "G") (pinfunction "G_G") (pintype "bidirectional"))
      (node (ref "R5") (pin "2") (pinfunction "2_2") (pintype "passive"))
      (node (ref "U1") (pin "43") (pinfunction "PB7(OC0A/OC1C/PCINT7)_43") (pintype "bidirectional"))
    )
    (net (code "38") (name "PWM2") (class "Default")
      (node (ref "J4") (pin "7") (pinfunction "7_7") (pintype "passive"))
      (node (ref "Q3") (pin "G") (pinfunction "G_G") (pintype "bidirectional"))
      (node (ref "R6") (pin "2") (pinfunction "2_2") (pintype "passive"))
      (node (ref "U1") (pin "42") (pinfunction "PB6(OC1B/PCINT6)_42") (pintype "bidirectional"))
    )
    (net (code "39") (name "PWM3") (class "Default")
      (node (ref "J4") (pin "8") (pinfunction "8_8") (pintype "passive"))
      (node (ref "Q4") (pin "G") (pinfunction "G_G") (pintype "bidirectional"))
      (node (ref "R7") (pin "2") (pinfunction "2_2") (pintype "passive"))
      (node (ref "U1") (pin "41") (pinfunction "PB5(OC1A/PCINT5)_41") (pintype "bidirectional"))
    )
    (net (code "40") (name "PWM4") (class "Default")
      (node (ref "J4") (pin "9") (pinfunction "9_9") (pintype "passive"))
      (node (ref "Q1") (pin "G") (pinfunction "G_G") (pintype "bidirectional"))
      (node (ref "R4") (pin "2") (pinfunction "2_2") (pintype "passive"))
      (node (ref "U1") (pin "40") (pinfunction "PB4(OC2A/PCINT4)_40") (pintype "bidirectional"))
    )
    (net (code "41") (name "RED") (class "Default")
      (node (ref "Q6") (pin "G") (pinfunction "G_G") (pintype "bidirectional"))
      (node (ref "R12") (pin "2") (pinfunction "2_2") (pintype "passive"))
      (node (ref "U1") (pin "19") (pinfunction "PG5(OC0B)_19") (pintype "bidirectional"))
    )
    (net (code "42") (name "RESET") (class "Default")
      (node (ref "C9") (pin "2") (pinfunction "2_2") (pintype "passive"))
      (node (ref "J1") (pin "5") (pinfunction "5_5") (pintype "passive"))
      (node (ref "R1") (pin "1") (pinfunction "1_1") (pintype "passive"))
      (node (ref "SW2") (pin "3") (pinfunction "2_3") (pintype "passive"))
      (node (ref "SW2") (pin "4") (pinfunction "2_4") (pintype "passive"))
      (node (ref "U1") (pin "12") (pinfunction "RSTN_12") (pintype "bidirectional"))
    )
    (net (code "43") (name "RX0") (class "Default")
      (node (ref "JP2") (pin "TXO") (pinfunction "3_TXO") (pintype "passive"))
      (node (ref "U1") (pin "46") (pinfunction "PE0(RXD0/PCINT8)_46") (pintype "bidirectional"))
    )
    (net (code "44") (name "SCK") (class "Default")
      (node (ref "J1") (pin "3") (pinfunction "3_3") (pintype "passive"))
      (node (ref "U1") (pin "37") (pinfunction "PB1(SCK/PCINT1)_37") (pintype "bidirectional"))
    )
    (net (code "45") (name "SCL") (class "Default")
      (node (ref "J2") (pin "3") (pinfunction "3_3") (pintype "bidirectional"))
      (node (ref "J4") (pin "4") (pinfunction "4_4") (pintype "passive"))
      (node (ref "R9") (pin "1") (pinfunction "1_1") (pintype "passive"))
      (node (ref "U1") (pin "25") (pinfunction "PD0(SCL/INT0)_25") (pintype "bidirectional"))
      (node (ref "U2") (pin "SCL/SPC") (pinfunction "SCL/SPC_SCL/SPC") (pintype "bidirectional"))
    )
    (net (code "46") (name "SDA") (class "Default")
      (node (ref "J2") (pin "4") (pinfunction "4_4") (pintype "bidirectional"))
      (node (ref "J4") (pin "2") (pinfunction "2_2") (pintype "passive"))
      (node (ref "R10") (pin "1") (pinfunction "1_1") (pintype "passive"))
      (node (ref "U1") (pin "26") (pinfunction "PD1(SDA/INT1)_26") (pintype "bidirectional"))
      (node (ref "U2") (pin "SDA/SDI/SDO") (pinfunction "SDA/SDI/SDO_SDA/SDI/SDO") (pintype "bidirectional"))
    )
    (net (code "47") (name "TX0") (class "Default")
      (node (ref "JP2") (pin "RXI") (pinfunction "2_RXI") (pintype "passive"))
      (node (ref "U1") (pin "47") (pinfunction "PE1(TXD0)_47") (pintype "bidirectional"))
    )
    (net (code "48") (name "VBAT") (class "Default")
      (node (ref "C10") (pin "1") (pinfunction "+_1") (pintype "passive"))
      (node (ref "C11") (pin "1") (pinfunction "+_1") (pintype "passive"))
      (node (ref "C12") (pin "1") (pinfunction "+_1") (pintype "passive"))
      (node (ref "C13") (pin "1") (pinfunction "+_1") (pintype "passive"))
      (node (ref "C15") (pin "1") (pinfunction "1_1") (pintype "passive"))
      (node (ref "D10") (pin "A") (pinfunction "A_A") (pintype "input"))
      (node (ref "D11") (pin "A") (pinfunction "A_A") (pintype "input"))
      (node (ref "D3") (pin "C") (pinfunction "C_C") (pintype "passive"))
      (node (ref "D4") (pin "C") (pinfunction "C_C") (pintype "passive"))
      (node (ref "D5") (pin "C") (pinfunction "C_C") (pintype "passive"))
      (node (ref "D6") (pin "C") (pinfunction "C_C") (pintype "passive"))
      (node (ref "D7") (pin "A") (pinfunction "A_A") (pintype "passive"))
      (node (ref "D8") (pin "A") (pinfunction "A_A") (pintype "input"))
      (node (ref "D9") (pin "A") (pinfunction "A_A") (pintype "bidirectional"))
      (node (ref "J3") (pin "1") (pinfunction "1_1") (pintype "passive"))
      (node (ref "J4") (pin "3") (pinfunction "3_3") (pintype "passive"))
      (node (ref "MP1") (pin "1") (pinfunction "V+_1") (pintype "bidirectional"))
      (node (ref "MP2") (pin "1") (pinfunction "V+_1") (pintype "bidirectional"))
      (node (ref "MP3") (pin "1") (pinfunction "V+_1") (pintype "bidirectional"))
      (node (ref "MP4") (pin "1") (pinfunction "V+_1") (pintype "bidirectional"))
      (node (ref "U3") (pin "1") (pinfunction "IN_1") (pintype "input"))
      (node (ref "U3") (pin "3") (pinfunction "EN_3") (pintype "input"))
    )
    (net (code "49") (name "YELLOW") (class "Default")
      (node (ref "Q7") (pin "G") (pinfunction "G_G") (pintype "bidirectional"))
      (node (ref "R13") (pin "2") (pinfunction "2_2") (pintype "passive"))
      (node (ref "U1") (pin "49") (pinfunction "PE3(OC3A/AIN1)_49") (pintype "bidirectional"))
    )
    (net (code "50") (name "unconnected-(J1-Pad2)") (class "Default")
      (node (ref "J1") (pin "2") (pinfunction "2_2") (pintype "passive"))
    )
    (net (code "51") (name "unconnected-(JP2-5-PadCTS)") (class "Default")
      (node (ref "JP2") (pin "CTS") (pinfunction "5_CTS") (pintype "passive"))
    )
    (net (code "52") (name "unconnected-(U1-AREF-Pad62)") (class "Default")
      (node (ref "U1") (pin "62") (pinfunction "AREF_62") (pintype "bidirectional"))
    )
    (net (code "53") (name "unconnected-(U1-PB0(SSN{slash}PCINT0)-Pad36)") (class "Default")
      (node (ref "U1") (pin "36") (pinfunction "PB0(SSN/PCINT0)_36") (pintype "bidirectional"))
    )
    (net (code "54") (name "unconnected-(U1-PD2(RXD1{slash}INT2)-Pad27)") (class "Default")
      (node (ref "U1") (pin "27") (pinfunction "PD2(RXD1/INT2)_27") (pintype "bidirectional"))
    )
    (net (code "55") (name "unconnected-(U1-PD3(TXD1{slash}INT3)-Pad28)") (class "Default")
      (node (ref "U1") (pin "28") (pinfunction "PD3(TXD1/INT3)_28") (pintype "bidirectional"))
    )
    (net (code "56") (name "unconnected-(U1-PD4(ICP1)-Pad29)") (class "Default")
      (node (ref "U1") (pin "29") (pinfunction "PD4(ICP1)_29") (pintype "bidirectional"))
    )
    (net (code "57") (name "unconnected-(U1-PD5(XCK1)-Pad30)") (class "Default")
      (node (ref "U1") (pin "30") (pinfunction "PD5(XCK1)_30") (pintype "bidirectional"))
    )
    (net (code "58") (name "unconnected-(U1-PD6(T1)-Pad31)") (class "Default")
      (node (ref "U1") (pin "31") (pinfunction "PD6(T1)_31") (pintype "bidirectional"))
    )
    (net (code "59") (name "unconnected-(U1-PD7(T0)-Pad32)") (class "Default")
      (node (ref "U1") (pin "32") (pinfunction "PD7(T0)_32") (pintype "bidirectional"))
    )
    (net (code "60") (name "unconnected-(U1-PE2(XCK0{slash}AIN0)-Pad48)") (class "Default")
      (node (ref "U1") (pin "48") (pinfunction "PE2(XCK0/AIN0)_48") (pintype "bidirectional"))
    )
    (net (code "61") (name "unconnected-(U1-PE6(T3{slash}INT6)-Pad52)") (class "Default")
      (node (ref "U1") (pin "52") (pinfunction "PE6(T3/INT6)_52") (pintype "bidirectional"))
    )
    (net (code "62") (name "unconnected-(U1-PE7(ICP3{slash}INT7{slash}CLKO)-Pad53)") (class "Default")
      (node (ref "U1") (pin "53") (pinfunction "PE7(ICP3/INT7/CLKO)_53") (pintype "bidirectional"))
    )
    (net (code "63") (name "unconnected-(U1-PF0(ADC0)-Pad63)") (class "Default")
      (node (ref "U1") (pin "63") (pinfunction "PF0(ADC0)_63") (pintype "bidirectional"))
    )
    (net (code "64") (name "unconnected-(U1-PF1(ADC1)-Pad64)") (class "Default")
      (node (ref "U1") (pin "64") (pinfunction "PF1(ADC1)_64") (pintype "bidirectional"))
    )
    (net (code "65") (name "unconnected-(U1-PF2(ADC2{slash}DIG2)-Pad1)") (class "Default")
      (node (ref "U1") (pin "1") (pinfunction "PF2(ADC2/DIG2)_1") (pintype "bidirectional"))
    )
    (net (code "66") (name "unconnected-(U1-PF3(ADC3{slash}DIG4)-Pad2)") (class "Default")
      (node (ref "U1") (pin "2") (pinfunction "PF3(ADC3/DIG4)_2") (pintype "bidirectional"))
    )
    (net (code "67") (name "unconnected-(U1-PF4(ADC4{slash}TCK)-Pad3)") (class "Default")
      (node (ref "U1") (pin "3") (pinfunction "PF4(ADC4/TCK)_3") (pintype "bidirectional"))
    )
    (net (code "68") (name "unconnected-(U1-PF5(ADC5{slash}TMS)-Pad4)") (class "Default")
      (node (ref "U1") (pin "4") (pinfunction "PF5(ADC5/TMS)_4") (pintype "bidirectional"))
    )
    (net (code "69") (name "unconnected-(U1-PF6(ADC6{slash}TDO)-Pad5)") (class "Default")
      (node (ref "U1") (pin "5") (pinfunction "PF6(ADC6/TDO)_5") (pintype "bidirectional"))
    )
    (net (code "70") (name "unconnected-(U1-PF7(ADC7{slash}TDI)-Pad6)") (class "Default")
      (node (ref "U1") (pin "6") (pinfunction "PF7(ADC7/TDI)_6") (pintype "bidirectional"))
    )
    (net (code "71") (name "unconnected-(U1-PG2(AMR)-Pad16)") (class "Default")
      (node (ref "U1") (pin "16") (pinfunction "PG2(AMR)_16") (pintype "bidirectional"))
    )
    (net (code "72") (name "unconnected-(U1-PG3(TOSC2)-Pad17)") (class "Default")
      (node (ref "U1") (pin "17") (pinfunction "PG3(TOSC2)_17") (pintype "bidirectional"))
    )
    (net (code "73") (name "unconnected-(U1-PG4(TOSC1)-Pad18)") (class "Default")
      (node (ref "U1") (pin "18") (pinfunction "PG4(TOSC1)_18") (pintype "bidirectional"))
    )
    (net (code "74") (name "unconnected-(U1-RSTON-Pad13)") (class "Default")
      (node (ref "U1") (pin "13") (pinfunction "RSTON_13") (pintype "bidirectional"))
    )
    (net (code "75") (name "unconnected-(U2-PadDRDY_M)") (class "Default")
      (node (ref "U2") (pin "DRDY_M") (pinfunction "DRDY_M_DRDY_M") (pintype "bidirectional"))
    )
    (net (code "76") (name "unconnected-(U2-PadINT1_A{slash}G)") (class "Default")
      (node (ref "U2") (pin "INT1_A/G") (pinfunction "INT1_A/G_INT1_A/G") (pintype "bidirectional"))
    )
    (net (code "77") (name "unconnected-(U2-PadINT2_A{slash}G)") (class "Default")
      (node (ref "U2") (pin "INT2_A/G") (pinfunction "INT2_A/G_INT2_A/G") (pintype "bidirectional"))
    )
    (net (code "78") (name "unconnected-(U2-PadINT_M)") (class "Default")
      (node (ref "U2") (pin "INT_M") (pinfunction "INT_M_INT_M") (pintype "bidirectional"))
    )
    (net (code "79") (name "unconnected-(U3-NC{slash}FB-Pad4)") (class "Default")
      (node (ref "U3") (pin "4") (pinfunction "NC/FB_4") (pintype "passive"))
    )
  )
)
